# sensor10DOF-S.net
KiCad netlist of a schematic drawn in Altium Designer
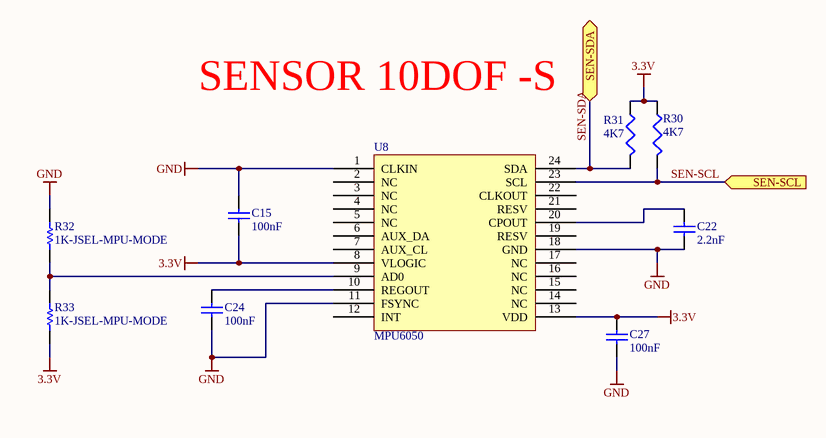
[diagram p0: sensor10DOF-S.SchDoc]

(export (version "E")
  (design (tool "Eeschema 10.0.6"))
  (components
    (comp (ref "C15")
      (value "100nF")
      (footprint "2012[0805]")
      (description "Capacitor")
      (fields (field (name "PUBLISHER") "Altium Limited"))
      (libsource (lib "Miscellaneous Devices") (part "Cap"))
    )
    (comp (ref "C22")
      (value "2.2nF")
      (footprint "2012[0805]")
      (description "Capacitor")
      (fields (field (name "PUBLISHER") "Altium Limited"))
      (libsource (lib "Miscellaneous Devices") (part "Cap"))
    )
    (comp (ref "C24")
      (value "100nF")
      (footprint "2012[0805]")
      (description "Capacitor")
      (fields (field (name "PUBLISHER") "Altium Limited"))
      (libsource (lib "Miscellaneous Devices") (part "Cap"))
    )
    (comp (ref "C27")
      (value "100nF")
      (footprint "2012[0805]")
      (description "Capacitor")
      (fields (field (name "PUBLISHER") "Altium Limited"))
      (libsource (lib "Miscellaneous Devices") (part "Cap"))
    )
    (comp (ref "R30")
      (value "4K7")
      (footprint "2012[0805]")
      (description "Resistor")
      (fields (field (name "PUBLISHER") "Altium Limited"))
      (libsource (lib "Miscellaneous Devices") (part "Res3"))
    )
    (comp (ref "R31")
      (value "4K7")
      (footprint "2012[0805]")
      (description "Resistor")
      (fields (field (name "PUBLISHER") "Altium Limited"))
      (libsource (lib "Miscellaneous Devices") (part "Res3"))
    )
    (comp (ref "R32")
      (value "1K-JSEL-MPU-MODE")
      (footprint "2012[0805]")
      (description "Resistor")
      (fields (field (name "PUBLISHER") "Altium Limited"))
      (libsource (lib "Miscellaneous Devices") (part "Res1"))
    )
    (comp (ref "R33")
      (value "1K-JSEL-MPU-MODE")
      (footprint "2012[0805]")
      (description "Resistor")
      (fields (field (name "PUBLISHER") "Altium Limited"))
      (libsource (lib "Miscellaneous Devices") (part "Res1"))
    )
    (comp (ref "U8") (value "MPU6050") (footprint "QFN_36") (libsource (lib "m") (part "MPU6050")))
  )
  (nets
    (net (code "1") (name "/SEN-SCL") (class "Default")
      (node (ref "R30") (pin "2") (pinfunction "2_2") (pintype "passive"))
      (node (ref "U8") (pin "23") (pinfunction "SCL_23") (pintype "passive"))
    )
    (net (code "2") (name "/SEN-SDA") (class "Default")
      (node (ref "R31") (pin "2") (pinfunction "2_2") (pintype "passive"))
      (node (ref "U8") (pin "24") (pinfunction "SDA_24") (pintype "passive"))
    )
    (net (code "3") (name "3.3V") (class "Default")
      (node (ref "C15") (pin "1") (pinfunction "1_1") (pintype "passive"))
      (node (ref "C27") (pin "2") (pinfunction "2_2") (pintype "passive"))
      (node (ref "R30") (pin "1") (pinfunction "1_1") (pintype "passive"))
      (node (ref "R31") (pin "1") (pinfunction "1_1") (pintype "passive"))
      (node (ref "R33") (pin "1") (pinfunction "1_1") (pintype "passive"))
      (node (ref "U8") (pin "13") (pinfunction "VDD_13") (pintype "passive"))
      (node (ref "U8") (pin "8") (pinfunction "VLOGIC_8") (pintype "passive"))
    )
    (net (code "4") (name "GND") (class "Default")
      (node (ref "C15") (pin "2") (pinfunction "2_2") (pintype "passive"))
      (node (ref "C22") (pin "1") (pinfunction "1_1") (pintype "passive"))
      (node (ref "C24") (pin "1") (pinfunction "1_1") (pintype "passive"))
      (node (ref "C27") (pin "1") (pinfunction "1_1") (pintype "passive"))
      (node (ref "R32") (pin "2") (pinfunction "2_2") (pintype "passive"))
      (node (ref "U8") (pin "1") (pinfunction "CLKIN_1") (pintype "passive"))
      (node (ref "U8") (pin "11") (pinfunction "FSYNC_11") (pintype "passive"))
      (node (ref "U8") (pin "18") (pinfunction "GND_18") (pintype "passive"))
    )
    (net (code "5") (name "Net-(U8-AD0)") (class "Default")
      (node (ref "R32") (pin "1") (pinfunction "1_1") (pintype "passive"))
      (node (ref "R33") (pin "2") (pinfunction "2_2") (pintype "passive"))
      (node (ref "U8") (pin "9") (pinfunction "AD0_9") (pintype "passive"))
    )
    (net (code "6") (name "Net-(U8-CPOUT)") (class "Default")
      (node (ref "C22") (pin "2") (pinfunction "2_2") (pintype "passive"))
      (node (ref "U8") (pin "20") (pinfunction "CPOUT_20") (pintype "passive"))
    )
    (net (code "7") (name "Net-(U8-REGOUT)") (class "Default")
      (node (ref "C24") (pin "2") (pinfunction "2_2") (pintype "passive"))
      (node (ref "U8") (pin "10") (pinfunction "REGOUT_10") (pintype "passive"))
    )
    (net (code "8") (name "unconnected-(U8-AUX_CL-Pad7)") (class "Default")
      (node (ref "U8") (pin "7") (pinfunction "AUX_CL_7") (pintype "passive"))
    )
    (net (code "9") (name "unconnected-(U8-AUX_DA-Pad6)") (class "Default")
      (node (ref "U8") (pin "6") (pinfunction "AUX_DA_6") (pintype "passive"))
    )
    (net (code "10") (name "unconnected-(U8-CLKOUT-Pad22)") (class "Default")
      (node (ref "U8") (pin "22") (pinfunction "CLKOUT_22") (pintype "passive"))
    )
    (net (code "11") (name "unconnected-(U8-INT-Pad12)") (class "Default")
      (node (ref "U8") (pin "12") (pinfunction "INT_12") (pintype "passive"))
    )
    (net (code "12") (name "unconnected-(U8-NC-Pad2)") (class "Default")
      (node (ref "U8") (pin "2") (pinfunction "NC_2") (pintype "passive"))
    )
    (net (code "13") (name "unconnected-(U8-NC-Pad3)") (class "Default")
      (node (ref "U8") (pin "3") (pinfunction "NC_3") (pintype "passive"))
    )
    (net (code "14") (name "unconnected-(U8-NC-Pad4)") (class "Default")
      (node (ref "U8") (pin "4") (pinfunction "NC_4") (pintype "passive"))
    )
    (net (code "15") (name "unconnected-(U8-NC-Pad5)") (class "Default")
      (node (ref "U8") (pin "5") (pinfunction "NC_5") (pintype "passive"))
    )
    (net (code "16") (name "unconnected-(U8-NC-Pad14)") (class "Default")
      (node (ref "U8") (pin "14") (pinfunction "NC_14") (pintype "passive"))
    )
    (net (code "17") (name "unconnected-(U8-NC-Pad15)") (class "Default")
      (node (ref "U8") (pin "15") (pinfunction "NC_15") (pintype "passive"))
    )
    (net (code "18") (name "unconnected-(U8-NC-Pad16)") (class "Default")
      (node (ref "U8") (pin "16") (pinfunction "NC_16") (pintype "passive"))
    )
    (net (code "19") (name "unconnected-(U8-NC-Pad17)") (class "Default")
      (node (ref "U8") (pin "17") (pinfunction "NC_17") (pintype "passive"))
    )
    (net (code "20") (name "unconnected-(U8-RESV-Pad19)") (class "Default")
      (node (ref "U8") (pin "19") (pinfunction "RESV_19") (pintype "passive"))
    )
    (net (code "21") (name "unconnected-(U8-RESV-Pad21)") (class "Default")
      (node (ref "U8") (pin "21") (pinfunction "RESV_21") (pintype "passive"))
    )
  )
)
